# v1_1_Power.net
KiCad netlist of a schematic drawn in EAGLE
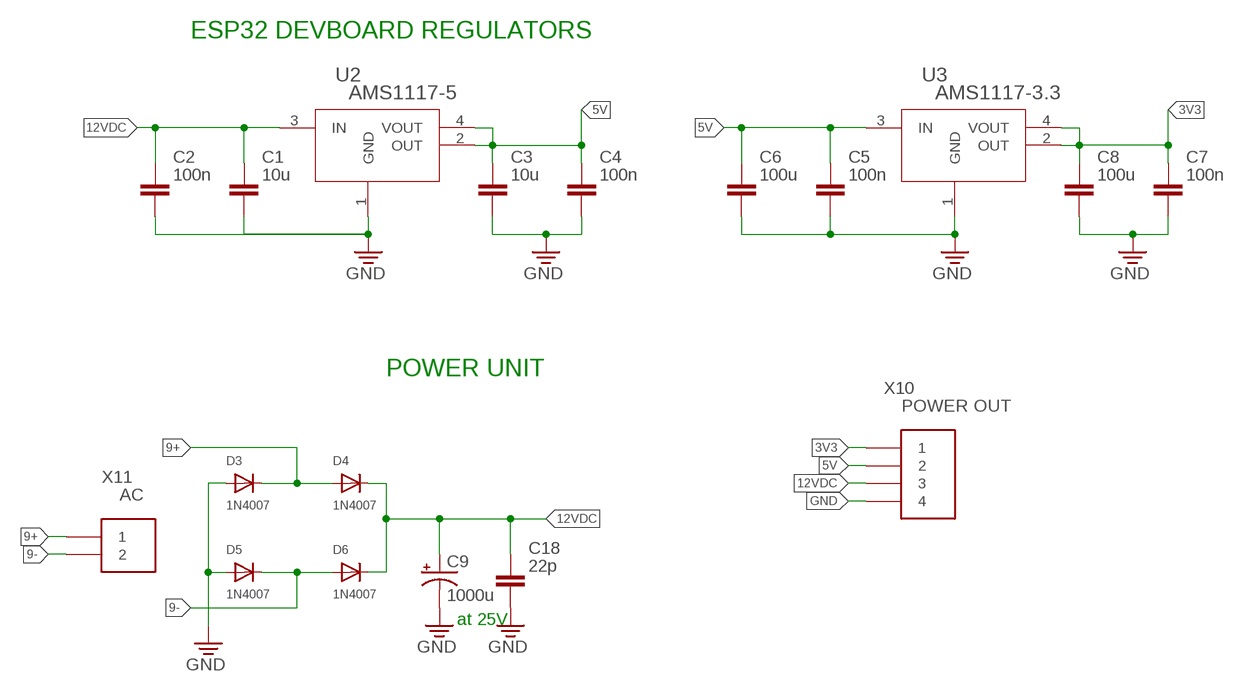
[diagram p0: schematic, sheet 1]

(export (version "E")
  (design (tool "Eeschema 10.0.6"))
  (components
    (comp (ref "C1")
      (value "10u")
      (footprint "eagle-import:CAPC2012X110")
      (libsource (lib "eagle-import") (part "CCHIP-0805(2012-METRIC)_"))
    )
    (comp (ref "C2")
      (value "100n")
      (footprint "eagle-import:CAPC2012X110")
      (libsource (lib "eagle-import") (part "CCHIP-0805(2012-METRIC)_"))
    )
    (comp (ref "C3")
      (value "10u")
      (footprint "eagle-import:CAPC2012X110")
      (libsource (lib "eagle-import") (part "CCHIP-0805(2012-METRIC)_"))
    )
    (comp (ref "C4")
      (value "100n")
      (footprint "eagle-import:CAPC2012X110")
      (libsource (lib "eagle-import") (part "CCHIP-0805(2012-METRIC)_"))
    )
    (comp (ref "C5")
      (value "100n")
      (footprint "eagle-import:CAPC2012X110")
      (libsource (lib "eagle-import") (part "CCHIP-0805(2012-METRIC)_"))
    )
    (comp (ref "C6")
      (value "100u")
      (footprint "eagle-import:CAPC2012X110")
      (libsource (lib "eagle-import") (part "CCHIP-0805(2012-METRIC)_"))
    )
    (comp (ref "C7")
      (value "100n")
      (footprint "eagle-import:CAPC2012X110")
      (libsource (lib "eagle-import") (part "CCHIP-0805(2012-METRIC)_"))
    )
    (comp (ref "C8")
      (value "100u")
      (footprint "eagle-import:CAPC2012X110")
      (libsource (lib "eagle-import") (part "CCHIP-0805(2012-METRIC)_"))
    )
    (comp (ref "C9")
      (value "1000u")
      (footprint "eagle-import:CAP_10X20IN")
      (fields
        (field (name "MANUFACTURER_PART_NUMBER") "UVR1E102MPD")
        (field (name "COPYRIGHT") "Copyright (C) 2025 Ultra Librarian. All rights reserved.")
      )
      (libsource (lib "eagle-import") (part "CAP_10X20INCAP_10X20IN"))
    )
    (comp (ref "C18")
      (value "22p")
      (footprint "eagle-import:CAPC2012X110")
      (libsource (lib "eagle-import") (part "CCHIP-0805(2012-METRIC)_"))
    )
    (comp (ref "D3")
      (value "1N4007")
      (footprint "eagle-import:SOD-123FL")
      (libsource (lib "eagle-import") (part "DIODE_SOD-123FL"))
    )
    (comp (ref "D4")
      (value "1N4007")
      (footprint "eagle-import:SOD-123FL")
      (libsource (lib "eagle-import") (part "DIODE_SOD-123FL"))
    )
    (comp (ref "D5")
      (value "1N4007")
      (footprint "eagle-import:SOD-123FL")
      (libsource (lib "eagle-import") (part "DIODE_SOD-123FL"))
    )
    (comp (ref "D6")
      (value "1N4007")
      (footprint "eagle-import:SOD-123FL")
      (libsource (lib "eagle-import") (part "DIODE_SOD-123FL"))
    )
    (comp (ref "U2")
      (value "AMS1117-5")
      (footprint "eagle-import:_AMS-L")
      (fields
        (field (name "MANUFACTURER_PART_NUMBER") "AMS1117-5.0")
        (field (name "COPYRIGHT") "Copyright (C) 2024 Ultra Librarian. All rights reserved.")
      )
      (libsource (lib "eagle-import") (part "AMS1117-5.0_AMS-L"))
    )
    (comp (ref "U3")
      (value "AMS1117-3.3")
      (footprint "eagle-import:_ADS-L")
      (fields (field (name "COPYRIGHT") "Copyright (C) 2024 Ultra Librarian. All rights reserved."))
      (libsource (lib "eagle-import") (part "AMS1117-3.3_ADS-L"))
    )
    (comp (ref "X10")
      (value "POWER OUT")
      (footprint "eagle-import:JST-XH-04-PACKAGE-LONG-PAD")
      (libsource (lib "eagle-import") (part "JST-XH-04-PIN-LONG-PAD"))
    )
    (comp (ref "X11")
      (value "AC")
      (footprint "eagle-import:-LONG-PAD")
      (libsource (lib "eagle-import") (part "JST-XH-02-PIN-LONG-PAD"))
    )
  )
  (nets
    (net (code "1") (name "3V3") (class "Default")
      (node (ref "C7") (pin "1") (pinfunction "1_1") (pintype "passive"))
      (node (ref "C8") (pin "1") (pinfunction "1_1") (pintype "passive"))
      (node (ref "U3") (pin "2") (pinfunction "OUT_2") (pintype "output"))
      (node (ref "U3") (pin "4") (pinfunction "VOUT_4") (pintype "power_in"))
      (node (ref "X10") (pin "1") (pinfunction "1_1") (pintype "passive"))
    )
    (net (code "2") (name "5V") (class "Default")
      (node (ref "C3") (pin "1") (pinfunction "1_1") (pintype "passive"))
      (node (ref "C4") (pin "1") (pinfunction "1_1") (pintype "passive"))
      (node (ref "C5") (pin "1") (pinfunction "1_1") (pintype "passive"))
      (node (ref "C6") (pin "1") (pinfunction "1_1") (pintype "passive"))
      (node (ref "U2") (pin "2") (pinfunction "OUT_2") (pintype "passive"))
      (node (ref "U2") (pin "4") (pinfunction "VOUT_4") (pintype "passive"))
      (node (ref "U3") (pin "3") (pinfunction "IN_3") (pintype "input"))
      (node (ref "X10") (pin "2") (pinfunction "2_2") (pintype "passive"))
    )
    (net (code "3") (name "9+") (class "Default")
      (node (ref "D3") (pin "C") (pinfunction "C_C") (pintype "passive"))
      (node (ref "D4") (pin "A") (pinfunction "A_A") (pintype "passive"))
      (node (ref "X11") (pin "1") (pinfunction "1_1") (pintype "passive"))
    )
    (net (code "4") (name "9-") (class "Default")
      (node (ref "D5") (pin "C") (pinfunction "C_C") (pintype "passive"))
      (node (ref "D6") (pin "A") (pinfunction "A_A") (pintype "passive"))
      (node (ref "X11") (pin "2") (pinfunction "2_2") (pintype "passive"))
    )
    (net (code "5") (name "12VDC") (class "Default")
      (node (ref "C1") (pin "1") (pinfunction "1_1") (pintype "passive"))
      (node (ref "C18") (pin "1") (pinfunction "1_1") (pintype "passive"))
      (node (ref "C2") (pin "1") (pinfunction "1_1") (pintype "passive"))
      (node (ref "C9") (pin "1") (pinfunction "+_1") (pintype "passive"))
      (node (ref "D4") (pin "C") (pinfunction "C_C") (pintype "passive"))
      (node (ref "D6") (pin "C") (pinfunction "C_C") (pintype "passive"))
      (node (ref "U2") (pin "3") (pinfunction "IN_3") (pintype "passive"))
      (node (ref "X10") (pin "3") (pinfunction "3_3") (pintype "passive"))
    )
    (net (code "6") (name "GND") (class "Default")
      (node (ref "C1") (pin "2") (pinfunction "2_2") (pintype "passive"))
      (node (ref "C18") (pin "2") (pinfunction "2_2") (pintype "passive"))
      (node (ref "C2") (pin "2") (pinfunction "2_2") (pintype "passive"))
      (node (ref "C3") (pin "2") (pinfunction "2_2") (pintype "passive"))
      (node (ref "C4") (pin "2") (pinfunction "2_2") (pintype "passive"))
      (node (ref "C5") (pin "2") (pinfunction "2_2") (pintype "passive"))
      (node (ref "C6") (pin "2") (pinfunction "2_2") (pintype "passive"))
      (node (ref "C7") (pin "2") (pinfunction "2_2") (pintype "passive"))
      (node (ref "C8") (pin "2") (pinfunction "2_2") (pintype "passive"))
      (node (ref "C9") (pin "2") (pinfunction "-_2") (pintype "passive"))
      (node (ref "D3") (pin "A") (pinfunction "A_A") (pintype "passive"))
      (node (ref "D5") (pin "A") (pinfunction "A_A") (pintype "passive"))
      (node (ref "U2") (pin "1") (pinfunction "GND_1") (pintype "passive"))
      (node (ref "U3") (pin "1") (pinfunction "GND_1") (pintype "passive"))
      (node (ref "X10") (pin "4") (pinfunction "4_4") (pintype "passive"))
    )
  )
)
